# Gesture.net
KiCad netlist of a schematic drawn in Altium Designer
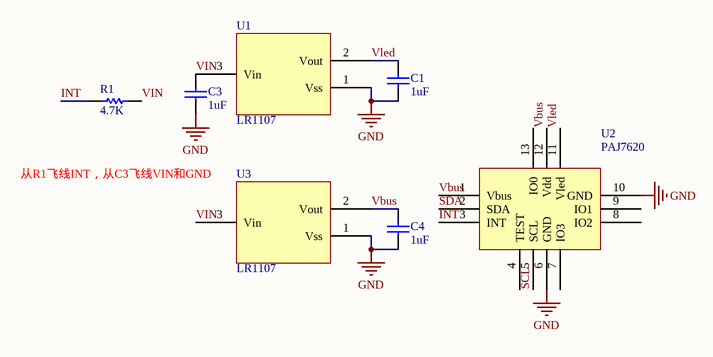
[diagram p0: Gesture.SchDoc]

(export (version "E")
  (design (tool "Eeschema 10.0.6"))
  (components
    (comp (ref "C1")
      (value "1uF")
      (footprint "C0603")
      (description "Capacitor")
      (fields (field (name "Comment") "0.1uF") (field (name "PUBLISHER") "Altium Limited"))
      (libsource (lib "显示盒子--sch封装库") (part "Cap"))
    )
    (comp (ref "C3")
      (value "1uF")
      (footprint "C0603")
      (description "Capacitor")
      (fields (field (name "Comment") "0.1uF") (field (name "PUBLISHER") "Altium Limited"))
      (libsource (lib "显示盒子--sch封装库") (part "Cap"))
    )
    (comp (ref "C4")
      (value "1uF")
      (footprint "C0603")
      (description "Capacitor")
      (fields (field (name "Comment") "0.1uF") (field (name "PUBLISHER") "Altium Limited"))
      (libsource (lib "显示盒子--sch封装库") (part "Cap"))
    )
    (comp (ref "R1")
      (value "4.7K")
      (footprint "0603-1")
      (description "Resistor")
      (fields (field (name "PUBLISHER") "Altium Limited"))
      (libsource (lib "显示盒子--sch封装库") (part "Res1"))
    )
    (comp (ref "U1") (value "LR1107") (footprint "SOT23A") (libsource (lib "ring") (part "XC6206")))
    (comp (ref "U2") (value "PAJ7620") (footprint "PAJ7620") (libsource (lib "ring") (part "PAJ7620")))
    (comp (ref "U3") (value "LR1107") (footprint "SOT23A") (libsource (lib "ring") (part "XC6206")))
  )
  (nets
    (net (code "1") (name "/INT") (class "Default")
      (node (ref "R1") (pin "1") (pinfunction "1_1") (pintype "passive"))
      (node (ref "U2") (pin "3") (pinfunction "INT_3") (pintype "passive"))
    )
    (net (code "2") (name "/SCL") (class "Default")
      (node (ref "U2") (pin "5") (pinfunction "SCL_5") (pintype "passive"))
    )
    (net (code "3") (name "/SDA") (class "Default")
      (node (ref "U2") (pin "2") (pinfunction "SDA_2") (pintype "passive"))
    )
    (net (code "4") (name "/VIN") (class "Default")
      (node (ref "C3") (pin "2") (pinfunction "2_2") (pintype "passive"))
      (node (ref "R1") (pin "2") (pinfunction "2_2") (pintype "passive"))
      (node (ref "U1") (pin "3") (pinfunction "Vin_3") (pintype "passive"))
      (node (ref "U3") (pin "3") (pinfunction "Vin_3") (pintype "passive"))
    )
    (net (code "5") (name "/Vbus") (class "Default")
      (node (ref "C4") (pin "2") (pinfunction "2_2") (pintype "passive"))
      (node (ref "U2") (pin "1") (pinfunction "Vbus_1") (pintype "passive"))
      (node (ref "U2") (pin "12") (pinfunction "Vdd_12") (pintype "passive"))
      (node (ref "U3") (pin "2") (pinfunction "Vout_2") (pintype "passive"))
    )
    (net (code "6") (name "/Vled") (class "Default")
      (node (ref "C1") (pin "2") (pinfunction "2_2") (pintype "passive"))
      (node (ref "U1") (pin "2") (pinfunction "Vout_2") (pintype "passive"))
      (node (ref "U2") (pin "11") (pinfunction "Vled_11") (pintype "passive"))
    )
    (net (code "7") (name "GND") (class "Default")
      (node (ref "C1") (pin "1") (pinfunction "1_1") (pintype "passive"))
      (node (ref "C3") (pin "1") (pinfunction "1_1") (pintype "passive"))
      (node (ref "C4") (pin "1") (pinfunction "1_1") (pintype "passive"))
      (node (ref "U1") (pin "1") (pinfunction "Vss_1") (pintype "passive"))
      (node (ref "U2") (pin "10") (pinfunction "GND_10") (pintype "passive"))
      (node (ref "U2") (pin "6") (pinfunction "GND_6") (pintype "passive"))
      (node (ref "U3") (pin "1") (pinfunction "Vss_1") (pintype "passive"))
    )
    (net (code "8") (name "unconnected-(U2-IO0-Pad13)") (class "Default")
      (node (ref "U2") (pin "13") (pinfunction "IO0_13") (pintype "passive"))
    )
    (net (code "9") (name "unconnected-(U2-IO1-Pad9)") (class "Default")
      (node (ref "U2") (pin "9") (pinfunction "IO1_9") (pintype "passive"))
    )
    (net (code "10") (name "unconnected-(U2-IO2-Pad8)") (class "Default")
      (node (ref "U2") (pin "8") (pinfunction "IO2_8") (pintype "passive"))
    )
    (net (code "11") (name "unconnected-(U2-IO3-Pad7)") (class "Default")
      (node (ref "U2") (pin "7") (pinfunction "IO3_7") (pintype "passive"))
    )
    (net (code "12") (name "unconnected-(U2-TEST-Pad4)") (class "Default")
      (node (ref "U2") (pin "4") (pinfunction "TEST_4") (pintype "passive"))
    )
  )
)
